# PCBBoardlayout.net
KiCad netlist of a schematic drawn in Altium Designer
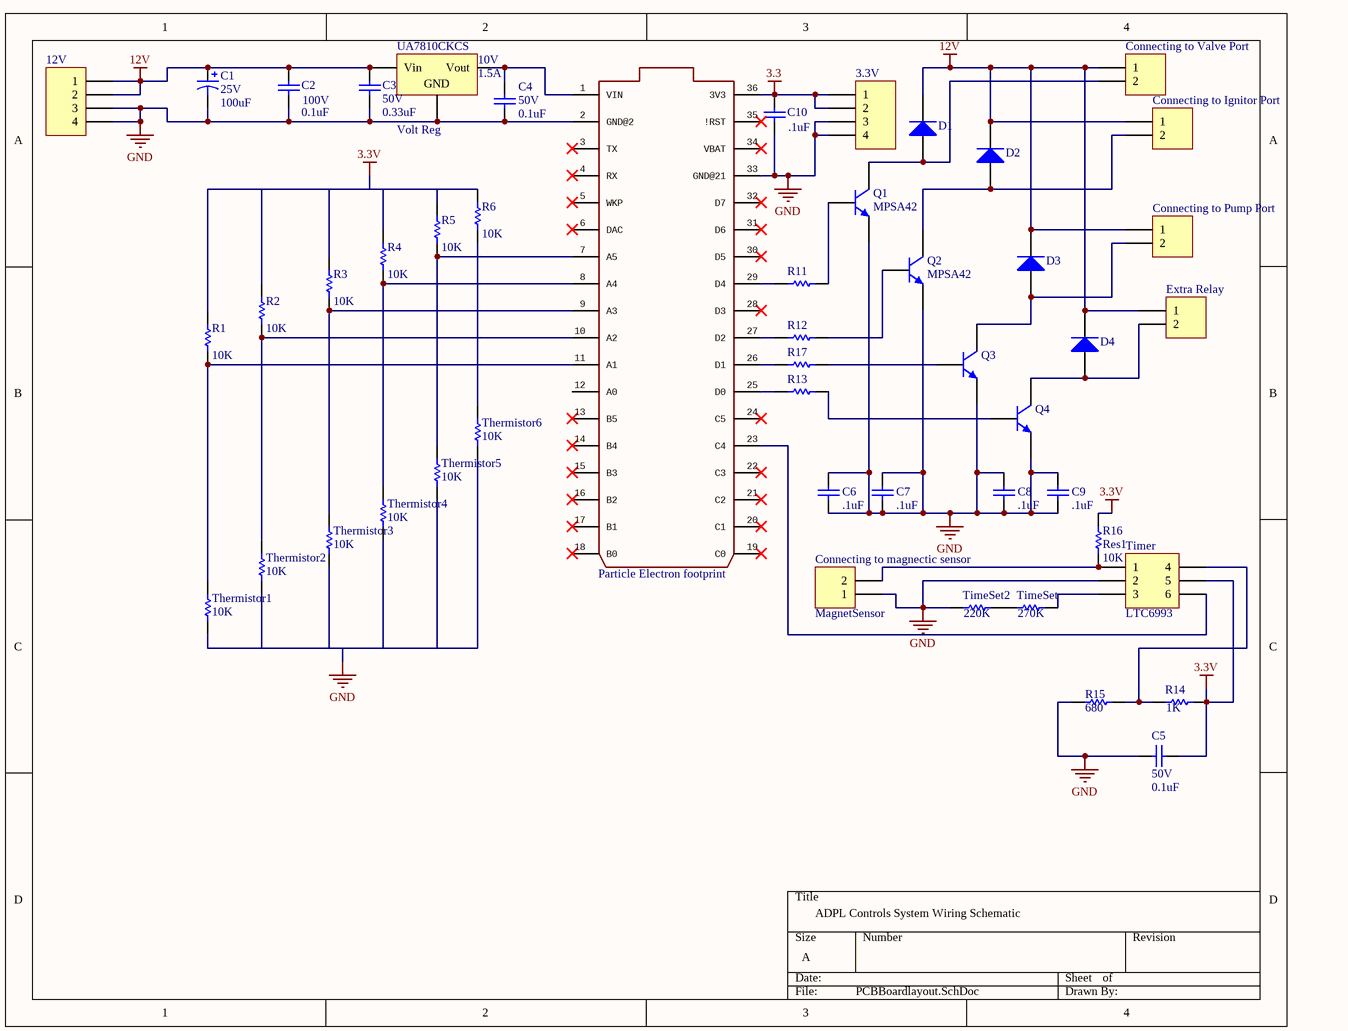
[diagram p0: PCBBoardlayout.SchDoc]

(export (version "E")
  (design (tool "Eeschema 10.0.6"))
  (components
    (comp (ref "3.3V")
      (value "~")
      (footprint "HDR1X4")
      (description "Header, 4-Pin")
      (fields (field (name "PUBLISHER") "Altium Limited"))
      (libsource (lib "") (part "Header 4_1"))
    )
    (comp (ref "12V")
      (value "~")
      (footprint "HDR1X2")
      (description "Header, 4-Pin")
      (fields (field (name "PUBLISHER") "Altium Limited"))
      (libsource (lib "Miscellaneous Connectors") (part "Header 4"))
    )
    (comp (ref "C1")
      (value "25V")
      (footprint "RB7.6-15")
      (description "Polarized Capacitor (Radial)")
      (fields (field (name "ALTIUM_VALUE") "100uF") (field (name "PUBLISHER") "Altium Limited"))
      (libsource (lib "Miscellaneous Devices") (part "Cap Pol1"))
    )
    (comp (ref "C2")
      (value "100V")
      (footprint "C1206")
      (description "Capacitor (Semiconductor SIM Model)")
      (fields
        (field (name "ALTIUM_VALUE") "0.1uF")
        (field (name "PART#") "581-SA111E104MAR")
        (field (name "PUBLISHER") "Altium Limited")
      )
      (libsource (lib "Miscellaneous Devices") (part "Cap Semi"))
    )
    (comp (ref "C3")
      (value "50V")
      (footprint "RAD-0.3")
      (description "Capacitor")
      (fields (field (name "ALTIUM_VALUE") "0.33uF") (field (name "PUBLISHER") "Altium Limited"))
      (libsource (lib "Miscellaneous Devices") (part "Cap"))
    )
    (comp (ref "C4")
      (value "50V")
      (footprint "RAD-0.3")
      (description "Capacitor")
      (fields (field (name "ALTIUM_VALUE") "0.1uF") (field (name "PUBLISHER") "Altium Limited"))
      (libsource (lib "Miscellaneous Devices") (part "Cap"))
    )
    (comp (ref "C5")
      (value "50V")
      (footprint "RAD-0.3")
      (description "Capacitor")
      (fields (field (name "ALTIUM_VALUE") "0.1uF") (field (name "PUBLISHER") "Altium Limited"))
      (libsource (lib "Miscellaneous Devices") (part "Cap"))
    )
    (comp (ref "C6")
      (value ".1uF")
      (footprint "C1206")
      (description "Capacitor (Semiconductor SIM Model)")
      (fields
        (field (name "PART#") "581-SA111E104MAR")
        (field (name "Comment") "BYCap")
        (field (name "PUBLISHER") "Altium Limited")
      )
      (libsource (lib "Miscellaneous Devices") (part "Cap Semi"))
    )
    (comp (ref "C7")
      (value ".1uF")
      (footprint "C1206")
      (description "Capacitor (Semiconductor SIM Model)")
      (fields
        (field (name "PART#") "581-SA111E104MAR")
        (field (name "Comment") "BYCap")
        (field (name "PUBLISHER") "Altium Limited")
      )
      (libsource (lib "Miscellaneous Devices") (part "Cap Semi"))
    )
    (comp (ref "C8")
      (value ".1uF")
      (footprint "C1206")
      (description "Capacitor (Semiconductor SIM Model)")
      (fields
        (field (name "PART#") "581-SA111E104MAR")
        (field (name "Comment") "BYCap")
        (field (name "PUBLISHER") "Altium Limited")
      )
      (libsource (lib "Miscellaneous Devices") (part "Cap Semi"))
    )
    (comp (ref "C9")
      (value ".1uF")
      (footprint "C1206")
      (description "Capacitor (Semiconductor SIM Model)")
      (fields
        (field (name "PART#") "581-SA111E104MAR")
        (field (name "Comment") "BYCap")
        (field (name "PUBLISHER") "Altium Limited")
      )
      (libsource (lib "Miscellaneous Devices") (part "Cap Semi"))
    )
    (comp (ref "C10")
      (value ".1uF")
      (footprint "C1206")
      (description "Capacitor (Semiconductor SIM Model)")
      (fields
        (field (name "PART#") "581-SA111E104MAR")
        (field (name "Comment") "BYCap")
        (field (name "PUBLISHER") "Altium Limited")
      )
      (libsource (lib "Miscellaneous Devices") (part "Cap Semi"))
    )
    (comp (ref "Connecting to Ignitor Port")
      (value "~")
      (footprint "HDR1X2")
      (description "Header, 2-Pin")
      (fields (field (name "PUBLISHER") "Altium Limited"))
      (libsource (lib "Miscellaneous Connectors") (part "Header 2"))
    )
    (comp (ref "Connecting to magnectic sensor")
      (value "MagnetSensor")
      (footprint "HDR1X2")
      (description "Header, 2-Pin")
      (fields
        (field (name "PUBLISHER") "Altium Limited")
        (field (name "SOURCE") "http://www.amazon.com/GERI-Counter-Digital-Proximity-Magnetic/dp/B01875612U/ref=sr_1_2?ie=UTF8&qid=1456764906&sr=8-2&keywords=magnetic+counter")
      )
      (libsource (lib "") (part "Header 2_1"))
    )
    (comp (ref "Connecting to Pump Port")
      (value "~")
      (footprint "HDR1X2")
      (description "Header, 2-Pin")
      (fields (field (name "PUBLISHER") "Altium Limited"))
      (libsource (lib "Miscellaneous Connectors") (part "Header 2"))
    )
    (comp (ref "Connecting to Valve Port")
      (value "~")
      (footprint "HDR1X2")
      (description "Header, 2-Pin")
      (fields (field (name "PUBLISHER") "Altium Limited"))
      (libsource (lib "Miscellaneous Connectors") (part "Header 2"))
    )
    (comp (ref "D1")
      (value "Diode 1N914")
      (footprint "DO-35")
      (description "High Conductance Fast Diode")
      (fields (field (name "PUBLISHER") "Altium Limited"))
      (libsource (lib "Miscellaneous Devices") (part "Diode 1N914"))
    )
    (comp (ref "D2")
      (value "Diode 1N914")
      (footprint "DO-35")
      (description "High Conductance Fast Diode")
      (fields (field (name "PUBLISHER") "Altium Limited"))
      (libsource (lib "Miscellaneous Devices") (part "Diode 1N914"))
    )
    (comp (ref "D3")
      (value "Diode 1N914")
      (footprint "DO-35")
      (description "High Conductance Fast Diode")
      (fields (field (name "PUBLISHER") "Altium Limited"))
      (libsource (lib "Miscellaneous Devices") (part "Diode 1N914"))
    )
    (comp (ref "D4")
      (value "Diode 1N914")
      (footprint "DO-35")
      (description "High Conductance Fast Diode")
      (fields (field (name "PUBLISHER") "Altium Limited"))
      (libsource (lib "Miscellaneous Devices") (part "Diode 1N914"))
    )
    (comp (ref "Extra Relay")
      (value "~")
      (footprint "HDR1X2")
      (description "Header, 2-Pin")
      (fields (field (name "PUBLISHER") "Altium Limited"))
      (libsource (lib "Miscellaneous Connectors") (part "Header 2"))
    )
    (comp (ref "Photon")
      (value "Particle Electron footprint")
      (footprint "ELECTRON")
      (libsource (lib "Particle-Devices") (part "ELECTRON_WITH_HEADERS"))
    )
    (comp (ref "Q1")
      (value "MPSA42")
      (footprint "Miscellaneous Devices:TO-92A")
      (description "NPN General Purpose Amplifier")
      (fields (field (name "PART#") "512-MPSA42") (field (name "PUBLISHER") "Altium Limited"))
      (libsource (lib "FSC Discrete BJT") (part "2N3904"))
    )
    (comp (ref "Q2")
      (value "MPSA42")
      (footprint "Miscellaneous Devices:TO-92A")
      (description "NPN General Purpose Amplifier")
      (fields (field (name "PART#") "512-MPSA42") (field (name "PUBLISHER") "Altium Limited"))
      (libsource (lib "FSC Discrete BJT") (part "2N3904"))
    )
    (comp (ref "Q3")
      (value "~")
      (footprint "Miscellaneous Devices:TO-92A")
      (description "NPN General Purpose Amplifier")
      (fields (field (name "PART#") "512-MPSA42") (field (name "PUBLISHER") "Altium Limited"))
      (libsource (lib "FSC Discrete BJT") (part "2N3904"))
    )
    (comp (ref "Q4")
      (value "MPSA42")
      (footprint "Miscellaneous Devices:TO-92A")
      (description "NPN General Purpose Amplifier")
      (fields (field (name "PART#") "512-MPSA42") (field (name "PUBLISHER") "Altium Limited"))
      (libsource (lib "FSC Discrete BJT") (part "2N3904"))
    )
    (comp (ref "R1")
      (value "10K")
      (footprint "AXIAL-0.3")
      (description "Resistor")
      (fields (field (name "Comment") "Res1") (field (name "PUBLISHER") "Altium Limited"))
      (libsource (lib "Miscellaneous Devices") (part "Res1"))
    )
    (comp (ref "R2")
      (value "10K")
      (footprint "AXIAL-0.3")
      (description "Resistor")
      (fields (field (name "Comment") "Res1") (field (name "PUBLISHER") "Altium Limited"))
      (libsource (lib "Miscellaneous Devices") (part "Res1"))
    )
    (comp (ref "R3")
      (value "10K")
      (footprint "AXIAL-0.3")
      (description "Resistor")
      (fields (field (name "Comment") "Res1") (field (name "PUBLISHER") "Altium Limited"))
      (libsource (lib "Miscellaneous Devices") (part "Res1"))
    )
    (comp (ref "R4")
      (value "10K")
      (footprint "AXIAL-0.3")
      (description "Resistor")
      (fields (field (name "Comment") "Res1") (field (name "PUBLISHER") "Altium Limited"))
      (libsource (lib "Miscellaneous Devices") (part "Res1"))
    )
    (comp (ref "R5")
      (value "10K")
      (footprint "AXIAL-0.3")
      (description "Resistor")
      (fields (field (name "Comment") "Res1") (field (name "PUBLISHER") "Altium Limited"))
      (libsource (lib "Miscellaneous Devices") (part "Res1"))
    )
    (comp (ref "R6")
      (value "10K")
      (footprint "AXIAL-0.3")
      (description "Resistor")
      (fields (field (name "Comment") "Res1") (field (name "PUBLISHER") "Altium Limited"))
      (libsource (lib "Miscellaneous Devices") (part "Res1"))
    )
    (comp (ref "R11")
      (value "Res1")
      (footprint "AXIAL-0.3")
      (description "Resistor")
      (fields (field (name "PUBLISHER") "Altium Limited"))
      (libsource (lib "Miscellaneous Devices") (part "Res1"))
    )
    (comp (ref "R12")
      (value "Res1")
      (footprint "AXIAL-0.3")
      (description "Resistor")
      (fields (field (name "PUBLISHER") "Altium Limited"))
      (libsource (lib "Miscellaneous Devices") (part "Res1"))
    )
    (comp (ref "R13")
      (value "Res1")
      (footprint "AXIAL-0.3")
      (description "Resistor")
      (fields (field (name "PUBLISHER") "Altium Limited"))
      (libsource (lib "Miscellaneous Devices") (part "Res1"))
    )
    (comp (ref "R14")
      (value "1K")
      (footprint "AXIAL-0.3")
      (description "Resistor")
      (fields
        (field (name "PART#") "660-CF1/4C681J")
        (field (name "Comment") "Res14")
        (field (name "PUBLISHER") "Altium Limited")
      )
      (libsource (lib "Miscellaneous Devices") (part "Res1"))
    )
    (comp (ref "R15")
      (value "680")
      (footprint "AXIAL-0.3")
      (description "Resistor")
      (fields
        (field (name "PART#") "660-CF1/4CT52R102J")
        (field (name "Comment") "Res1")
        (field (name "PUBLISHER") "Altium Limited")
      )
      (libsource (lib "Miscellaneous Devices") (part "Res1"))
    )
    (comp (ref "R16")
      (value "Res1")
      (footprint "AXIAL-0.3")
      (description "Resistor")
      (fields (field (name "ALTIUM_VALUE") "10K") (field (name "PUBLISHER") "Altium Limited"))
      (libsource (lib "Miscellaneous Devices") (part "Res1"))
    )
    (comp (ref "R17")
      (value "Res1")
      (footprint "AXIAL-0.3")
      (description "Resistor")
      (fields (field (name "PUBLISHER") "Altium Limited"))
      (libsource (lib "Miscellaneous Devices") (part "Res1"))
    )
    (comp (ref "Thermistor1")
      (value "10K")
      (footprint "AXIAL-0.3")
      (description "Resistor")
      (fields
        (field (name "PART#") "NTCAIMME3C90373")
        (field (name "Comment") "Res1")
        (field (name "PUBLISHER") "Altium Limited")
      )
      (libsource (lib "Miscellaneous Devices") (part "Res1"))
    )
    (comp (ref "Thermistor2")
      (value "10K")
      (footprint "AXIAL-0.3")
      (description "Resistor")
      (fields
        (field (name "PART#") "NTCAIMME3C90373")
        (field (name "Comment") "Res1")
        (field (name "PUBLISHER") "Altium Limited")
      )
      (libsource (lib "Miscellaneous Devices") (part "Res1"))
    )
    (comp (ref "Thermistor3")
      (value "10K")
      (footprint "AXIAL-0.3")
      (description "Resistor")
      (fields
        (field (name "PART#") "Dwyer I2-1B062")
        (field (name "Comment") "Res1")
        (field (name "PUBLISHER") "Altium Limited")
      )
      (libsource (lib "Miscellaneous Devices") (part "Res1"))
    )
    (comp (ref "Thermistor4")
      (value "10K")
      (footprint "AXIAL-0.3")
      (description "Resistor")
      (fields
        (field (name "PART#") "NTCAIMME3C90373")
        (field (name "Comment") "Res1")
        (field (name "PUBLISHER") "Altium Limited")
      )
      (libsource (lib "Miscellaneous Devices") (part "Res1"))
    )
    (comp (ref "Thermistor5")
      (value "10K")
      (footprint "AXIAL-0.3")
      (description "Resistor")
      (fields
        (field (name "PART#") "NTCAIMME3C90373")
        (field (name "Comment") "Res1")
        (field (name "PUBLISHER") "Altium Limited")
      )
      (libsource (lib "Miscellaneous Devices") (part "Res1"))
    )
    (comp (ref "Thermistor6")
      (value "10K")
      (footprint "AXIAL-0.3")
      (description "Resistor")
      (fields
        (field (name "PART#") "NTCAIMME3C90373")
        (field (name "Comment") "Res1")
        (field (name "PUBLISHER") "Altium Limited")
      )
      (libsource (lib "Miscellaneous Devices") (part "Res1"))
    )
    (comp (ref "Timer")
      (value "LTC6993")
      (footprint "PCB_Footprints:LTC6993")
      (libsource (lib "custom_components") (part "LTC6993"))
    )
    (comp (ref "TimeSet")
      (value "270K")
      (footprint "AXIAL-0.3")
      (description "Resistor")
      (fields
        (field (name "PART#") "660-CF1/4CT52R274J")
        (field (name "Comment") "Res1")
        (field (name "PUBLISHER") "Altium Limited")
      )
      (libsource (lib "Miscellaneous Devices") (part "Res1"))
    )
    (comp (ref "TimeSet2")
      (value "220K")
      (footprint "AXIAL-0.3")
      (description "Resistor")
      (fields
        (field (name "PART#") "660-CF1/4CT52R224J")
        (field (name "Comment") "Res1")
        (field (name "PUBLISHER") "Altium Limited")
      )
      (libsource (lib "Miscellaneous Devices") (part "Res1"))
    )
    (comp (ref "UA7810CKCS")
      (value "Volt Reg")
      (footprint "D2PAK_N")
      (description "Voltage Regulator")
      (fields
        (field (name "PART#") "UA7810CKCS")
        (field (name "VOLTAGE OUTPUT") "10V")
        (field (name "CURRENT OUTPUT") "1.5A")
        (field (name "PUBLISHER") "Altium Limited")
      )
      (libsource (lib "Miscellaneous Devices") (part "Volt Reg"))
    )
  )
  (nets
    (net (code "1") (name "3.3") (class "Default")
      (node (ref "3.3V") (pin "1") (pinfunction "1_1") (pintype "passive"))
      (node (ref "3.3V") (pin "2") (pinfunction "2_2") (pintype "passive"))
      (node (ref "C10") (pin "2") (pinfunction "2_2") (pintype "passive"))
      (node (ref "Photon") (pin "36") (pinfunction "3V3_36") (pintype "power_in"))
    )
    (net (code "2") (name "3.3V") (class "Default")
      (node (ref "C5") (pin "1") (pinfunction "1_1") (pintype "passive"))
      (node (ref "R14") (pin "1") (pinfunction "1_1") (pintype "passive"))
      (node (ref "R16") (pin "2") (pinfunction "2_2") (pintype "passive"))
      (node (ref "Timer") (pin "5") (pinfunction "5_5") (pintype "passive"))
    )
    (net (code "3") (name "12V") (class "Default")
      (node (ref "12V") (pin "1") (pinfunction "1_1") (pintype "passive"))
      (node (ref "12V") (pin "2") (pinfunction "2_2") (pintype "passive"))
      (node (ref "C1") (pin "1") (pinfunction "1_1") (pintype "passive"))
      (node (ref "C2") (pin "2") (pinfunction "2_2") (pintype "passive"))
      (node (ref "C3") (pin "2") (pinfunction "2_2") (pintype "passive"))
      (node (ref "Connecting to Ignitor Port") (pin "1") (pinfunction "1_1") (pintype "passive"))
      (node (ref "Connecting to Pump Port") (pin "1") (pinfunction "1_1") (pintype "passive"))
      (node (ref "Connecting to Valve Port") (pin "1") (pinfunction "1_1") (pintype "passive"))
      (node (ref "D1") (pin "2") (pinfunction "K_2") (pintype "passive"))
      (node (ref "D2") (pin "2") (pinfunction "K_2") (pintype "passive"))
      (node (ref "D3") (pin "2") (pinfunction "K_2") (pintype "passive"))
      (node (ref "D4") (pin "2") (pinfunction "K_2") (pintype "passive"))
      (node (ref "Extra Relay") (pin "1") (pinfunction "1_1") (pintype "passive"))
      (node (ref "UA7810CKCS") (pin "1") (pinfunction "Vin_1") (pintype "passive"))
    )
    (net (code "4") (name "GND") (class "Default")
      (node (ref "12V") (pin "3") (pinfunction "3_3") (pintype "passive"))
      (node (ref "12V") (pin "4") (pinfunction "4_4") (pintype "passive"))
      (node (ref "3.3V") (pin "3") (pinfunction "3_3") (pintype "passive"))
      (node (ref "3.3V") (pin "4") (pinfunction "4_4") (pintype "passive"))
      (node (ref "C1") (pin "2") (pinfunction "2_2") (pintype "passive"))
      (node (ref "C10") (pin "1") (pinfunction "1_1") (pintype "passive"))
      (node (ref "C2") (pin "1") (pinfunction "1_1") (pintype "passive"))
      (node (ref "C3") (pin "1") (pinfunction "1_1") (pintype "passive"))
      (node (ref "C4") (pin "1") (pinfunction "1_1") (pintype "passive"))
      (node (ref "C5") (pin "2") (pinfunction "2_2") (pintype "passive"))
      (node (ref "C6") (pin "1") (pinfunction "1_1") (pintype "passive"))
      (node (ref "C6") (pin "2") (pinfunction "2_2") (pintype "passive"))
      (node (ref "C7") (pin "1") (pinfunction "1_1") (pintype "passive"))
      (node (ref "C7") (pin "2") (pinfunction "2_2") (pintype "passive"))
      (node (ref "C8") (pin "1") (pinfunction "1_1") (pintype "passive"))
      (node (ref "C8") (pin "2") (pinfunction "2_2") (pintype "passive"))
      (node (ref "C9") (pin "1") (pinfunction "1_1") (pintype "passive"))
      (node (ref "C9") (pin "2") (pinfunction "2_2") (pintype "passive"))
      (node (ref "Connecting to magnectic sensor") (pin "1") (pinfunction "1_1") (pintype "passive"))
      (node (ref "Photon") (pin "2") (pinfunction "GND@2_2") (pintype "power_in"))
      (node (ref "Photon") (pin "33") (pinfunction "GND@21_33") (pintype "power_in"))
      (node (ref "Q1") (pin "1") (pinfunction "E_1") (pintype "passive"))
      (node (ref "Q2") (pin "1") (pinfunction "E_1") (pintype "passive"))
      (node (ref "Q3") (pin "1") (pinfunction "E_1") (pintype "passive"))
      (node (ref "Q4") (pin "1") (pinfunction "E_1") (pintype "passive"))
      (node (ref "R15") (pin "2") (pinfunction "2_2") (pintype "passive"))
      (node (ref "TimeSet2") (pin "1") (pinfunction "1_1") (pintype "passive"))
      (node (ref "Timer") (pin "2") (pinfunction "2_2") (pintype "passive"))
      (node (ref "UA7810CKCS") (pin "2") (pinfunction "GND_2") (pintype "passive"))
    )
    (net (code "5") (name "Net-(Connecting to magnectic sensor-Pad2)") (class "Default")
      (node (ref "Connecting to magnectic sensor") (pin "2") (pinfunction "2_2") (pintype "passive"))
      (node (ref "R16") (pin "1") (pinfunction "1_1") (pintype "passive"))
      (node (ref "Timer") (pin "1") (pinfunction "1_1") (pintype "passive"))
    )
    (net (code "6") (name "Net-(D1-A)") (class "Default")
      (node (ref "Connecting to Valve Port") (pin "2") (pinfunction "2_2") (pintype "passive"))
      (node (ref "D1") (pin "1") (pinfunction "A_1") (pintype "passive"))
      (node (ref "Q1") (pin "3") (pinfunction "C_3") (pintype "passive"))
    )
    (net (code "7") (name "Net-(D2-A)") (class "Default")
      (node (ref "Connecting to Ignitor Port") (pin "2") (pinfunction "2_2") (pintype "passive"))
      (node (ref "D2") (pin "1") (pinfunction "A_1") (pintype "passive"))
      (node (ref "Q2") (pin "3") (pinfunction "C_3") (pintype "passive"))
    )
    (net (code "8") (name "Net-(D3-A)") (class "Default")
      (node (ref "Connecting to Pump Port") (pin "2") (pinfunction "2_2") (pintype "passive"))
      (node (ref "D3") (pin "1") (pinfunction "A_1") (pintype "passive"))
      (node (ref "Q3") (pin "3") (pinfunction "C_3") (pintype "passive"))
    )
    (net (code "9") (name "Net-(D4-A)") (class "Default")
      (node (ref "D4") (pin "1") (pinfunction "A_1") (pintype "passive"))
      (node (ref "Extra Relay") (pin "2") (pinfunction "2_2") (pintype "passive"))
      (node (ref "Q4") (pin "3") (pinfunction "C_3") (pintype "passive"))
    )
    (net (code "10") (name "Net-(Photon-A1)") (class "Default")
      (node (ref "Photon") (pin "11") (pinfunction "A1_11") (pintype "passive"))
      (node (ref "R1") (pin "1") (pinfunction "1_1") (pintype "passive"))
      (node (ref "Thermistor1") (pin "2") (pinfunction "2_2") (pintype "passive"))
    )
    (net (code "11") (name "Net-(Photon-A2)") (class "Default")
      (node (ref "Photon") (pin "10") (pinfunction "A2_10") (pintype "passive"))
      (node (ref "R2") (pin "1") (pinfunction "1_1") (pintype "passive"))
      (node (ref "Thermistor2") (pin "2") (pinfunction "2_2") (pintype "passive"))
    )
    (net (code "12") (name "Net-(Photon-A3)") (class "Default")
      (node (ref "Photon") (pin "9") (pinfunction "A3_9") (pintype "passive"))
      (node (ref "R3") (pin "1") (pinfunction "1_1") (pintype "passive"))
      (node (ref "Thermistor3") (pin "2") (pinfunction "2_2") (pintype "passive"))
    )
    (net (code "13") (name "Net-(Photon-A4)") (class "Default")
      (node (ref "Photon") (pin "8") (pinfunction "A4_8") (pintype "passive"))
      (node (ref "R4") (pin "1") (pinfunction "1_1") (pintype "passive"))
      (node (ref "Thermistor4") (pin "2") (pinfunction "2_2") (pintype "passive"))
    )
    (net (code "14") (name "Net-(Photon-A5)") (class "Default")
      (node (ref "Photon") (pin "7") (pinfunction "A5_7") (pintype "passive"))
      (node (ref "R5") (pin "1") (pinfunction "1_1") (pintype "passive"))
      (node (ref "Thermistor5") (pin "2") (pinfunction "2_2") (pintype "passive"))
    )
    (net (code "15") (name "Net-(Photon-C4)") (class "Default")
      (node (ref "Photon") (pin "23") (pinfunction "C4_23") (pintype "passive"))
      (node (ref "Timer") (pin "6") (pinfunction "6_6") (pintype "passive"))
    )
    (net (code "16") (name "Net-(Photon-D0)") (class "Default")
      (node (ref "Photon") (pin "25") (pinfunction "D0_25") (pintype "passive"))
      (node (ref "R13") (pin "1") (pinfunction "1_1") (pintype "passive"))
    )
    (net (code "17") (name "Net-(Photon-D1)") (class "Default")
      (node (ref "Photon") (pin "26") (pinfunction "D1_26") (pintype "passive"))
      (node (ref "R17") (pin "1") (pinfunction "1_1") (pintype "passive"))
    )
    (net (code "18") (name "Net-(Photon-D2)") (class "Default")
      (node (ref "Photon") (pin "27") (pinfunction "D2_27") (pintype "passive"))
      (node (ref "R12") (pin "1") (pinfunction "1_1") (pintype "passive"))
    )
    (net (code "19") (name "Net-(Photon-D4)") (class "Default")
      (node (ref "Photon") (pin "29") (pinfunction "D4_29") (pintype "passive"))
      (node (ref "R11") (pin "1") (pinfunction "1_1") (pintype "passive"))
    )
    (net (code "20") (name "Net-(Photon-VIN)") (class "Default")
      (node (ref "C4") (pin "2") (pinfunction "2_2") (pintype "passive"))
      (node (ref "Photon") (pin "1") (pinfunction "VIN_1") (pintype "power_in"))
      (node (ref "UA7810CKCS") (pin "3") (pinfunction "Vout_3") (pintype "passive"))
    )
    (net (code "21") (name "Net-(Q1-B)") (class "Default")
      (node (ref "Q1") (pin "2") (pinfunction "B_2") (pintype "passive"))
      (node (ref "R11") (pin "2") (pinfunction "2_2") (pintype "passive"))
    )
    (net (code "22") (name "Net-(Q2-B)") (class "Default")
      (node (ref "Q2") (pin "2") (pinfunction "B_2") (pintype "passive"))
      (node (ref "R12") (pin "2") (pinfunction "2_2") (pintype "passive"))
    )
    (net (code "23") (name "Net-(Q3-B)") (class "Default")
      (node (ref "Q3") (pin "2") (pinfunction "B_2") (pintype "passive"))
      (node (ref "R17") (pin "2") (pinfunction "2_2") (pintype "passive"))
    )
    (net (code "24") (name "Net-(Q4-B)") (class "Default")
      (node (ref "Q4") (pin "2") (pinfunction "B_2") (pintype "passive"))
      (node (ref "R13") (pin "2") (pinfunction "2_2") (pintype "passive"))
    )
    (net (code "25") (name "Net-(R6-Pad1)") (class "Default")
      (node (ref "R6") (pin "1") (pinfunction "1_1") (pintype "passive"))
      (node (ref "Thermistor6") (pin "2") (pinfunction "2_2") (pintype "passive"))
    )
    (net (code "26") (name "Net-(R14-Pad2)") (class "Default")
      (node (ref "R14") (pin "2") (pinfunction "2_2") (pintype "passive"))
      (node (ref "R15") (pin "1") (pinfunction "1_1") (pintype "passive"))
      (node (ref "Timer") (pin "4") (pinfunction "4_4") (pintype "passive"))
    )
    (net (code "27") (name "Net-(TimeSet-Pad1)") (class "Default")
      (node (ref "TimeSet") (pin "1") (pinfunction "1_1") (pintype "passive"))
      (node (ref "TimeSet2") (pin "2") (pinfunction "2_2") (pintype "passive"))
    )
    (net (code "28") (name "Net-(TimeSet-Pad2)") (class "Default")
      (node (ref "TimeSet") (pin "2") (pinfunction "2_2") (pintype "passive"))
      (node (ref "Timer") (pin "3") (pinfunction "3_3") (pintype "passive"))
    )
    (net (code "29") (name "unconnected-(Photon-!RST-Pad35)") (class "Default")
      (node (ref "Photon") (pin "35") (pinfunction "!RST_35") (pintype "passive+no_connect"))
    )
    (net (code "30") (name "unconnected-(Photon-A0-Pad12)") (class "Default")
      (node (ref "Photon") (pin "12") (pinfunction "A0_12") (pintype "passive"))
    )
    (net (code "31") (name "unconnected-(Photon-B0-Pad18)") (class "Default")
      (node (ref "Photon") (pin "18") (pinfunction "B0_18") (pintype "passive+no_connect"))
    )
    (net (code "32") (name "unconnected-(Photon-B1-Pad17)") (class "Default")
      (node (ref "Photon") (pin "17") (pinfunction "B1_17") (pintype "passive+no_connect"))
    )
    (net (code "33") (name "unconnected-(Photon-B2-Pad16)") (class "Default")
      (node (ref "Photon") (pin "16") (pinfunction "B2_16") (pintype "passive+no_connect"))
    )
    (net (code "34") (name "unconnected-(Photon-B3-Pad15)") (class "Default")
      (node (ref "Photon") (pin "15") (pinfunction "B3_15") (pintype "passive+no_connect"))
    )
    (net (code "35") (name "unconnected-(Photon-B4-Pad14)") (class "Default")
      (node (ref "Photon") (pin "14") (pinfunction "B4_14") (pintype "passive+no_connect"))
    )
    (net (code "36") (name "unconnected-(Photon-B5-Pad13)") (class "Default")
      (node (ref "Photon") (pin "13") (pinfunction "B5_13") (pintype "passive+no_connect"))
    )
    (net (code "37") (name "unconnected-(Photon-C0-Pad19)") (class "Default")
      (node (ref "Photon") (pin "19") (pinfunction "C0_19") (pintype "passive+no_connect"))
    )
    (net (code "38") (name "unconnected-(Photon-C1-Pad20)") (class "Default")
      (node (ref "Photon") (pin "20") (pinfunction "C1_20") (pintype "passive+no_connect"))
    )
    (net (code "39") (name "unconnected-(Photon-C2-Pad21)") (class "Default")
      (node (ref "Photon") (pin "21") (pinfunction "C2_21") (pintype "passive+no_connect"))
    )
    (net (code "40") (name "unconnected-(Photon-C3-Pad22)") (class "Default")
      (node (ref "Photon") (pin "22") (pinfunction "C3_22") (pintype "passive+no_connect"))
    )
    (net (code "41") (name "unconnected-(Photon-C5-Pad24)") (class "Default")
      (node (ref "Photon") (pin "24") (pinfunction "C5_24") (pintype "passive+no_connect"))
    )
    (net (code "42") (name "unconnected-(Photon-D3-Pad28)") (class "Default")
      (node (ref "Photon") (pin "28") (pinfunction "D3_28") (pintype "passive+no_connect"))
    )
    (net (code "43") (name "unconnected-(Photon-D5-Pad30)") (class "Default")
      (node (ref "Photon") (pin "30") (pinfunction "D5_30") (pintype "passive+no_connect"))
    )
    (net (code "44") (name "unconnected-(Photon-D6-Pad31)") (class "Default")
      (node (ref "Photon") (pin "31") (pinfunction "D6_31") (pintype "passive+no_connect"))
    )
    (net (code "45") (name "unconnected-(Photon-D7-Pad32)") (class "Default")
      (node (ref "Photon") (pin "32") (pinfunction "D7_32") (pintype "passive+no_connect"))
    )
    (net (code "46") (name "unconnected-(Photon-DAC-Pad6)") (class "Default")
      (node (ref "Photon") (pin "6") (pinfunction "DAC_6") (pintype "passive+no_connect"))
    )
    (net (code "47") (name "unconnected-(Photon-RX-Pad4)") (class "Default")
      (node (ref "Photon") (pin "4") (pinfunction "RX_4") (pintype "passive+no_connect"))
    )
    (net (code "48") (name "unconnected-(Photon-TX-Pad3)") (class "Default")
      (node (ref "Photon") (pin "3") (pinfunction "TX_3") (pintype "passive+no_connect"))
    )
    (net (code "49") (name "unconnected-(Photon-VBAT-Pad34)") (class "Default")
      (node (ref "Photon") (pin "34") (pinfunction "VBAT_34") (pintype "power_in+no_connect"))
    )
    (net (code "50") (name "unconnected-(Photon-WKP-Pad5)") (class "Default")
      (node (ref "Photon") (pin "5") (pinfunction "WKP_5") (pintype "passive+no_connect"))
    )
    (net (code "51") (name "unconnected-(R1-Pad2)") (class "Default")
      (node (ref "R1") (pin "2") (pinfunction "2_2") (pintype "passive"))
    )
    (net (code "52") (name "unconnected-(R2-Pad2)") (class "Default")
      (node (ref "R2") (pin "2") (pinfunction "2_2") (pintype "passive"))
    )
    (net (code "53") (name "unconnected-(R3-Pad2)") (class "Default")
      (node (ref "R3") (pin "2") (pinfunction "2_2") (pintype "passive"))
    )
    (net (code "54") (name "unconnected-(R4-Pad2)") (class "Default")
      (node (ref "R4") (pin "2") (pinfunction "2_2") (pintype "passive"))
    )
    (net (code "55") (name "unconnected-(R5-Pad2)") (class "Default")
      (node (ref "R5") (pin "2") (pinfunction "2_2") (pintype "passive"))
    )
    (net (code "56") (name "unconnected-(R6-Pad2)") (class "Default")
      (node (ref "R6") (pin "2") (pinfunction "2_2") (pintype "passive"))
    )
    (net (code "57") (name "unconnected-(Thermistor1-Pad1)") (class "Default")
      (node (ref "Thermistor1") (pin "1") (pinfunction "1_1") (pintype "passive"))
    )
    (net (code "58") (name "unconnected-(Thermistor2-Pad1)") (class "Default")
      (node (ref "Thermistor2") (pin "1") (pinfunction "1_1") (pintype "passive"))
    )
    (net (code "59") (name "unconnected-(Thermistor3-Pad1)") (class "Default")
      (node (ref "Thermistor3") (pin "1") (pinfunction "1_1") (pintype "passive"))
    )
    (net (code "60") (name "unconnected-(Thermistor4-Pad1)") (class "Default")
      (node (ref "Thermistor4") (pin "1") (pinfunction "1_1") (pintype "passive"))
    )
    (net (code "61") (name "unconnected-(Thermistor5-Pad1)") (class "Default")
      (node (ref "Thermistor5") (pin "1") (pinfunction "1_1") (pintype "passive"))
    )
    (net (code "62") (name "unconnected-(Thermistor6-Pad1)") (class "Default")
      (node (ref "Thermistor6") (pin "1") (pinfunction "1_1") (pintype "passive"))
    )
  )
)
